# GRLV_double_Rail_v0_2b_P2.net
KiCad netlist of a schematic drawn in Altium Designer
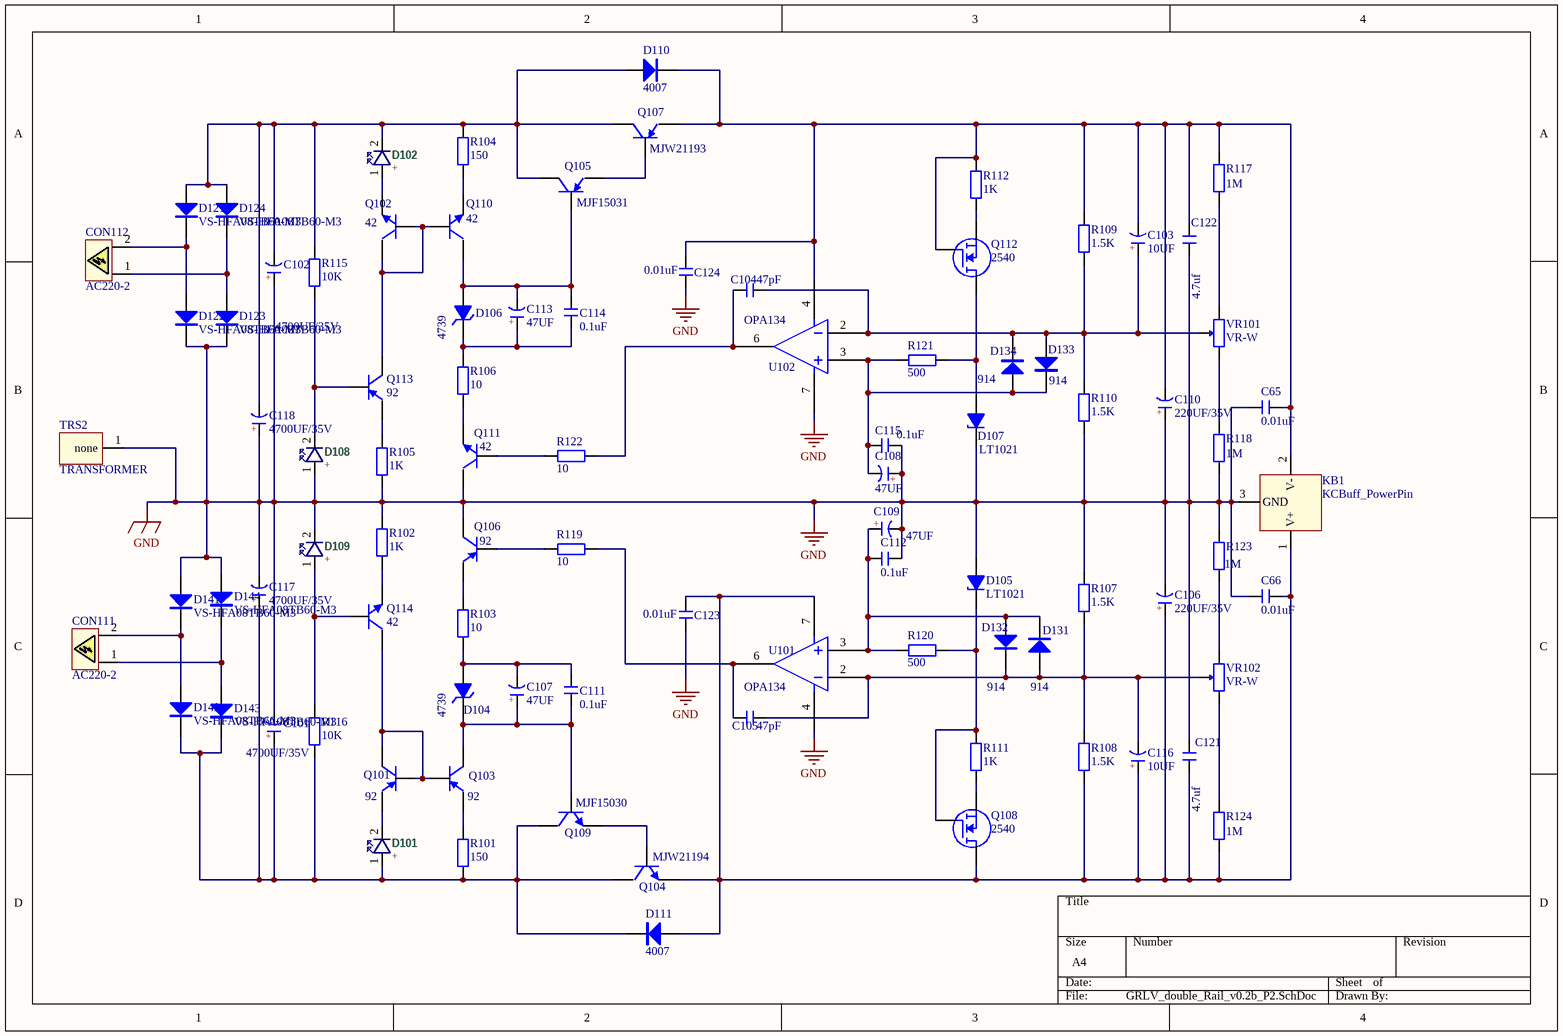
[diagram p0: GRLV_double_Rail_v0.2b_P2.SchDoc]

(export (version "E")
  (design (tool "Eeschema 10.0.6"))
  (components
    (comp (ref "C65")
      (value "0.01uF")
      (footprint "CBB 6.3*6.3*5")
      (description "CBB电容")
      (fields (field (name "版权归属") "源创客"))
      (libsource (lib "电阻-电容-电感") (part "C-CBB"))
    )
    (comp (ref "C66")
      (value "0.01uF")
      (footprint "CBB 6.3*6.3*5")
      (description "CBB电容")
      (fields (field (name "版权归属") "源创客"))
      (libsource (lib "电阻-电容-电感") (part "C-CBB"))
    )
    (comp (ref "C101")
      (value "4700UF/35V")
      (footprint "CAP 10*22*31.5")
      (description "直插电解电容")
      (fields (field (name "版权归属") "源创客"))
      (libsource (lib "电阻-电容-电感") (part "C-CAP"))
    )
    (comp (ref "C102")
      (value "4700UF/35V")
      (footprint "CAP 10*22*31.5")
      (description "直插电解电容")
      (fields (field (name "版权归属") "源创客"))
      (libsource (lib "电阻-电容-电感") (part "C-CAP"))
    )
    (comp (ref "C103")
      (value "10UF")
      (footprint "CAP 2.5*6.3*7")
      (description "直插电解电容")
      (fields (field (name "版权归属") "源创客"))
      (libsource (lib "电阻-电容-电感") (part "C-CAP"))
    )
    (comp (ref "C104")
      (value "47pF")
      (footprint "CBB 6.3*6.3*5")
      (description "CBB电容")
      (fields (field (name "版权归属") "源创客"))
      (libsource (lib "电阻-电容-电感") (part "C-CBB"))
    )
    (comp (ref "C105")
      (value "47pF")
      (footprint "CBB 6.3*6.3*5")
      (description "CBB电容")
      (fields (field (name "版权归属") "源创客"))
      (libsource (lib "电阻-电容-电感") (part "C-CBB"))
    )
    (comp (ref "C106")
      (value "220UF/35V")
      (footprint "CAP 5.0*10*12.5")
      (description "直插电解电容")
      (fields (field (name "版权归属") "源创客"))
      (libsource (lib "电阻-电容-电感") (part "C-CAP"))
    )
    (comp (ref "C107")
      (value "47UF")
      (footprint "CAP 3.5*8*11.5")
      (description "直插电解电容")
      (fields (field (name "版权归属") "源创客"))
      (libsource (lib "电阻-电容-电感") (part "C-CAP"))
    )
    (comp (ref "C108")
      (value "47UF")
      (footprint "CAP 2.5*6.3*11.2")
      (description "直插电解电容")
      (fields (field (name "版权归属") "源创客"))
      (libsource (lib "") (part "C-CAP_1"))
    )
    (comp (ref "C109")
      (value "47UF")
      (footprint "CAP 2.5*6.3*11.2")
      (description "直插电解电容")
      (fields (field (name "版权归属") "源创客"))
      (libsource (lib "") (part "C-CAP_1"))
    )
    (comp (ref "C110")
      (value "220UF/35V")
      (footprint "CAP 5.0*10*12.5")
      (description "直插电解电容")
      (fields (field (name "版权归属") "源创客"))
      (libsource (lib "电阻-电容-电感") (part "C-CAP"))
    )
    (comp (ref "C111")
      (value "0.1uF")
      (footprint "CBB 6.3*6.3*5")
      (description "CBB电容")
      (fields (field (name "版权归属") "源创客"))
      (libsource (lib "电阻-电容-电感") (part "C-CBB"))
    )
    (comp (ref "C112")
      (value "0.1uF")
      (footprint "CBB 6.3*6.3*5")
      (description "CBB电容")
      (fields (field (name "版权归属") "源创客"))
      (libsource (lib "电阻-电容-电感") (part "C-CBB"))
    )
    (comp (ref "C113")
      (value "47UF")
      (footprint "CAP 3.5*8*11.5")
      (description "直插电解电容")
      (fields (field (name "版权归属") "源创客"))
      (libsource (lib "电阻-电容-电感") (part "C-CAP"))
    )
    (comp (ref "C114")
      (value "0.1uF")
      (footprint "CBB 6.3*6.3*5")
      (description "CBB电容")
      (fields (field (name "版权归属") "源创客"))
      (libsource (lib "电阻-电容-电感") (part "C-CBB"))
    )
    (comp (ref "C115")
      (value "0.1uF")
      (footprint "CBB 6.3*6.3*5")
      (description "CBB电容")
      (fields (field (name "版权归属") "源创客"))
      (libsource (lib "电阻-电容-电感") (part "C-CBB"))
    )
    (comp (ref "C116")
      (value "10UF")
      (footprint "CAP 2.5*6.3*7")
      (description "直插电解电容")
      (fields (field (name "版权归属") "源创客"))
      (libsource (lib "电阻-电容-电感") (part "C-CAP"))
    )
    (comp (ref "C117")
      (value "4700UF/35V")
      (footprint "CAP 10*22*31.5")
      (description "直插电解电容")
      (fields (field (name "版权归属") "源创客"))
      (libsource (lib "电阻-电容-电感") (part "C-CAP"))
    )
    (comp (ref "C118")
      (value "4700UF/35V")
      (footprint "CAP 10*22*31.5")
      (description "直插电解电容")
      (fields (field (name "版权归属") "源创客"))
      (libsource (lib "电阻-电容-电感") (part "C-CAP"))
    )
    (comp (ref "C121")
      (value "4.7uf")
      (footprint "CBB 7.2*7.2*13")
      (description "MKS薄膜电容")
      (libsource (lib "电阻-电容-电感") (part "C-MKS"))
    )
    (comp (ref "C122")
      (value "4.7uf")
      (footprint "CBB 7.2*7.2*13")
      (description "MKS薄膜电容")
      (libsource (lib "电阻-电容-电感") (part "C-MKS"))
    )
    (comp (ref "C123")
      (value "0.01uF")
      (footprint "CBB 6.3*6.3*5")
      (description "CBB电容")
      (fields (field (name "Comment") ".01") (field (name "版权归属") "源创客"))
      (libsource (lib "电阻-电容-电感") (part "C-CBB"))
    )
    (comp (ref "C124")
      (value "0.01uF")
      (footprint "CBB 6.3*6.3*5")
      (description "CBB电容")
      (fields (field (name "Comment") ".01") (field (name "版权归属") "源创客"))
      (libsource (lib "电阻-电容-电感") (part "C-CBB"))
    )
    (comp (ref "CON111")
      (value "AC220-2")
      (footprint "HX4.0-2XS")
      (libsource (lib "Connectors") (part "AC220-2"))
    )
    (comp (ref "CON112")
      (value "AC220-2")
      (footprint "HX4.0-2XS")
      (libsource (lib "Connectors") (part "AC220-2"))
    )
    (comp (ref "D101")
      (value "+")
      (footprint "LED 3MM-R")
      (description "直插式LED")
      (libsource (lib "LED") (part "LED"))
    )
    (comp (ref "D102")
      (value "+")
      (footprint "LED 3MM-R")
      (description "直插式LED")
      (libsource (lib "LED") (part "LED"))
    )
    (comp (ref "D104")
      (value "4739")
      (footprint "DO-41")
      (description "9.1V/1W稳压管")
      (libsource (lib "二极管-整流桥") (part "1N4739"))
    )
    (comp (ref "D105")
      (value "LT1021")
      (footprint "DIP8-300_MH")
      (description "10V Precision Reference 2 Pin Config")
      (libsource (lib "电压参考") (part "LT1021-10-2P"))
    )
    (comp (ref "D106")
      (value "4739")
      (footprint "DO-41")
      (description "9.1V/1W稳压管")
      (libsource (lib "二极管-整流桥") (part "1N4739"))
    )
    (comp (ref "D107")
      (value "LT1021")
      (footprint "DIP8-300_MH")
      (description "10V Precision Reference 2 Pin Config")
      (libsource (lib "电压参考") (part "LT1021-10-2P"))
    )
    (comp (ref "D108")
      (value "+")
      (footprint "LED 3MM-R")
      (description "直插式LED")
      (libsource (lib "LED") (part "LED"))
    )
    (comp (ref "D109")
      (value "+")
      (footprint "LED 3MM-R")
      (description "直插式LED")
      (libsource (lib "LED") (part "LED"))
    )
    (comp (ref "D110")
      (value "4007")
      (footprint "DO-41")
      (description "整流二极管")
      (fields (field (name "版权归属") "源创客"))
      (libsource (lib "二极管-整流桥") (part "1N4007"))
    )
    (comp (ref "D111")
      (value "4007")
      (footprint "DO-41")
      (description "整流二极管")
      (fields (field (name "版权归属") "源创客"))
      (libsource (lib "二极管-整流桥") (part "1N4007"))
    )
    (comp (ref "D121")
      (value "VS-HFA08TB60-M3")
      (footprint "DO-15XL")
      (description "Ultrafast Soft Recovery Diado 8A 600V")
      (libsource (lib "二极管-整流桥") (part "VS-HFA08TB60-M3"))
    )
    (comp (ref "D122")
      (value "VS-HFA08TB60-M3")
      (footprint "DO-15XL")
      (description "Ultrafast Soft Recovery Diado 8A 600V")
      (libsource (lib "二极管-整流桥") (part "VS-HFA08TB60-M3"))
    )
    (comp (ref "D123")
      (value "VS-HFA08TB60-M3")
      (footprint "DO-15XL")
      (description "Ultrafast Soft Recovery Diado 8A 600V")
      (libsource (lib "二极管-整流桥") (part "VS-HFA08TB60-M3"))
    )
    (comp (ref "D124")
      (value "VS-HFA08TB60-M3")
      (footprint "DO-15XL")
      (description "Ultrafast Soft Recovery Diado 8A 600V")
      (libsource (lib "二极管-整流桥") (part "VS-HFA08TB60-M3"))
    )
    (comp (ref "D131")
      (value "914")
      (footprint "DO-35")
      (description "高速开关管 1V/0.25W")
      (libsource (lib "二极管-整流桥") (part "1N914"))
    )
    (comp (ref "D132")
      (value "914")
      (footprint "DO-35")
      (description "高速开关管 1V/0.25W")
      (libsource (lib "二极管-整流桥") (part "1N914"))
    )
    (comp (ref "D133")
      (value "914")
      (footprint "DO-35")
      (description "高速开关管 1V/0.25W")
      (libsource (lib "二极管-整流桥") (part "1N914"))
    )
    (comp (ref "D134")
      (value "914")
      (footprint "DO-35")
      (description "高速开关管 1V/0.25W")
      (libsource (lib "二极管-整流桥") (part "1N914"))
    )
    (comp (ref "D141")
      (value "VS-HFA08TB60-M3")
      (footprint "DO-15XL")
      (description "Ultrafast Soft Recovery Diado 8A 600V")
      (libsource (lib "二极管-整流桥") (part "VS-HFA08TB60-M3"))
    )
    (comp (ref "D142")
      (value "VS-HFA08TB60-M3")
      (footprint "DO-15XL")
      (description "Ultrafast Soft Recovery Diado 8A 600V")
      (libsource (lib "二极管-整流桥") (part "VS-HFA08TB60-M3"))
    )
    (comp (ref "D143")
      (value "VS-HFA08TB60-M3")
      (footprint "DO-15XL")
      (description "Ultrafast Soft Recovery Diado 8A 600V")
      (libsource (lib "二极管-整流桥") (part "VS-HFA08TB60-M3"))
    )
    (comp (ref "D144")
      (value "VS-HFA08TB60-M3")
      (footprint "DO-15XL")
      (description "Ultrafast Soft Recovery Diado 8A 600V")
      (libsource (lib "二极管-整流桥") (part "VS-HFA08TB60-M3"))
    )
    (comp (ref "KB1")
      (value "KCBuff_PowerPin")
      (footprint "KCBuff_PowerPin_M4")
      (description "King Cello Buffer Stage")
      (libsource (lib "KC_amp") (part "KCBuff_PowerPin"))
    )
    (comp (ref "Q101")
      (value "92")
      (footprint "TO92A")
      (description "High Voltage PNP Transistor")
      (libsource (lib "三极管") (part "KSP92/93"))
    )
    (comp (ref "Q102")
      (value "42")
      (footprint "TO92A")
      (description "High Voltage NPN Transistor")
      (libsource (lib "三极管") (part "KSP42/43"))
    )
    (comp (ref "Q103")
      (value "92")
      (footprint "TO92A")
      (description "High Voltage PNP Transistor")
      (libsource (lib "三极管") (part "KSP92/93"))
    )
    (comp (ref "Q104")
      (value "MJW21194")
      (footprint "TO247V")
      (description "Power NPN Transistor")
      (libsource (lib "三极管") (part "MJW21194"))
    )
    (comp (ref "Q105")
      (value "MJF15031")
      (footprint "TO220V")
      (description "Power PNP Transistor")
      (libsource (lib "三极管") (part "MJF15031"))
    )
    (comp (ref "Q106")
      (value "92")
      (footprint "TO92A")
      (description "High Voltage PNP Transistor")
      (libsource (lib "三极管") (part "KSP92/93"))
    )
    (comp (ref "Q107")
      (value "MJW21193")
      (footprint "TO247V")
      (description "Power PNP Transistor")
      (libsource (lib "三极管") (part "MJW21193"))
    )
    (comp (ref "Q108")
      (value "2540")
      (footprint "TO92A")
      (description "N沟道耗尽型DMOS场效应管 400V/150ma")
      (libsource (lib "场效应管") (part "DN2540"))
    )
    (comp (ref "Q109")
      (value "MJF15030")
      (footprint "TO220V")
      (description "Power NPN Transistor")
      (libsource (lib "三极管") (part "MJF15030"))
    )
    (comp (ref "Q110")
      (value "42")
      (footprint "TO92A")
      (description "High Voltage NPN Transistor")
      (libsource (lib "三极管") (part "KSP42/43"))
    )
    (comp (ref "Q111")
      (value "42")
      (footprint "TO92A")
      (description "High Voltage NPN Transistor")
      (libsource (lib "三极管") (part "KSP42/43"))
    )
    (comp (ref "Q112")
      (value "2540")
      (footprint "TO92A")
      (description "N沟道耗尽型DMOS场效应管 400V/150ma")
      (libsource (lib "场效应管") (part "DN2540"))
    )
    (comp (ref "Q113")
      (value "92")
      (footprint "TO92A")
      (description "High Voltage PNP Transistor")
      (libsource (lib "三极管") (part "KSP92/93"))
    )
    (comp (ref "Q114")
      (value "42")
      (footprint "TO92A")
      (description "High Voltage NPN Transistor")
      (libsource (lib "三极管") (part "KSP42/43"))
    )
    (comp (ref "R101")
      (value "150")
      (footprint "RS 1/4W")
      (description "直插色环电阻")
      (fields (field (name "版权归属") "源创客"))
      (libsource (lib "电阻-电容-电感") (part "R-CRR"))
    )
    (comp (ref "R102")
      (value "1K")
      (footprint "RS 1/4W")
      (description "直插色环电阻")
      (fields (field (name "版权归属") "源创客"))
      (libsource (lib "电阻-电容-电感") (part "R-CRR"))
    )
    (comp (ref "R103")
      (value "10")
      (footprint "RS 1/4W")
      (description "直插色环电阻")
      (fields (field (name "版权归属") "源创客"))
      (libsource (lib "电阻-电容-电感") (part "R-CRR"))
    )
    (comp (ref "R104")
      (value "150")
      (footprint "RS 1/4W")
      (description "直插色环电阻")
      (fields (field (name "版权归属") "源创客"))
      (libsource (lib "电阻-电容-电感") (part "R-CRR"))
    )
    (comp (ref "R105")
      (value "1K")
      (footprint "RS 1/4W")
      (description "直插色环电阻")
      (fields (field (name "版权归属") "源创客"))
      (libsource (lib "电阻-电容-电感") (part "R-CRR"))
    )
    (comp (ref "R106")
      (value "10")
      (footprint "RS 1/4W")
      (description "直插色环电阻")
      (fields (field (name "版权归属") "源创客"))
      (libsource (lib "电阻-电容-电感") (part "R-CRR"))
    )
    (comp (ref "R107")
      (value "1.5K")
      (footprint "RS 1/4W")
      (description "直插色环电阻")
      (fields (field (name "版权归属") "源创客"))
      (libsource (lib "电阻-电容-电感") (part "R-CRR"))
    )
    (comp (ref "R108")
      (value "1.5K")
      (footprint "RS 1/4W")
      (description "直插色环电阻")
      (fields (field (name "版权归属") "源创客"))
      (libsource (lib "电阻-电容-电感") (part "R-CRR"))
    )
    (comp (ref "R109")
      (value "1.5K")
      (footprint "RS 1/4W")
      (description "直插色环电阻")
      (fields (field (name "版权归属") "源创客"))
      (libsource (lib "电阻-电容-电感") (part "R-CRR"))
    )
    (comp (ref "R110")
      (value "1.5K")
      (footprint "RS 1/4W")
      (description "直插色环电阻")
      (fields (field (name "版权归属") "源创客"))
      (libsource (lib "电阻-电容-电感") (part "R-CRR"))
    )
    (comp (ref "R111")
      (value "1K")
      (footprint "RS 1/4W")
      (description "直插色环电阻")
      (fields (field (name "版权归属") "源创客"))
      (libsource (lib "电阻-电容-电感") (part "R-CRR"))
    )
    (comp (ref "R112")
      (value "1K")
      (footprint "RS 1/4W")
      (description "直插色环电阻")
      (fields (field (name "版权归属") "源创客"))
      (libsource (lib "电阻-电容-电感") (part "R-CRR"))
    )
    (comp (ref "R115")
      (value "10K")
      (footprint "RS 1/4W")
      (description "直插色环电阻")
      (fields (field (name "版权归属") "源创客"))
      (libsource (lib "电阻-电容-电感") (part "R-CRR"))
    )
    (comp (ref "R116")
      (value "10K")
      (footprint "RS 1/4W")
      (description "直插色环电阻")
      (fields (field (name "版权归属") "源创客"))
      (libsource (lib "电阻-电容-电感") (part "R-CRR"))
    )
    (comp (ref "R117")
      (value "1M")
      (footprint "RS 1/4W")
      (description "直插色环电阻")
      (fields (field (name "版权归属") "源创客"))
      (libsource (lib "电阻-电容-电感") (part "R-CRR"))
    )
    (comp (ref "R118")
      (value "1M")
      (footprint "RS 1/4W")
      (description "直插色环电阻")
      (fields (field (name "版权归属") "源创客"))
      (libsource (lib "电阻-电容-电感") (part "R-CRR"))
    )
    (comp (ref "R119")
      (value "10")
      (footprint "RS 1/4W")
      (description "直插色环电阻")
      (fields (field (name "版权归属") "源创客"))
      (libsource (lib "电阻-电容-电感") (part "R-CRR"))
    )
    (comp (ref "R120")
      (value "500")
      (footprint "RS 1/4W")
      (description "直插色环电阻")
      (fields (field (name "版权归属") "源创客"))
      (libsource (lib "电阻-电容-电感") (part "R-CRR"))
    )
    (comp (ref "R121")
      (value "500")
      (footprint "RS 1/4W")
      (description "直插色环电阻")
      (fields (field (name "版权归属") "源创客"))
      (libsource (lib "电阻-电容-电感") (part "R-CRR"))
    )
    (comp (ref "R122")
      (value "10")
      (footprint "RS 1/4W")
      (description "直插色环电阻")
      (fields (field (name "版权归属") "源创客"))
      (libsource (lib "电阻-电容-电感") (part "R-CRR"))
    )
    (comp (ref "R123")
      (value "1M")
      (footprint "RS 1/4W")
      (description "直插色环电阻")
      (fields (field (name "版权归属") "源创客"))
      (libsource (lib "电阻-电容-电感") (part "R-CRR"))
    )
    (comp (ref "R124")
      (value "1M")
      (footprint "RS 1/4W")
      (description "直插色环电阻")
      (fields (field (name "版权归属") "源创客"))
      (libsource (lib "电阻-电容-电感") (part "R-CRR"))
    )
    (comp (ref "TRS2")
      (value "TRANSFORMER")
      (footprint "TRANS_BLOCK_30W_24v")
      (description "Transformer")
      (libsource (lib "KC_amp") (part "TRANSFORMER"))
    )
    (comp (ref "U101") (value "OPA134") (footprint "DIP8-300_MH") (libsource (lib "运放") (part "OPA134PA")))
    (comp (ref "U102") (value "OPA134") (footprint "DIP8-300_MH") (libsource (lib "运放") (part "OPA134PA")))
    (comp (ref "VR101")
      (value "VR-W")
      (footprint "RS 1/2W-VR")
      (description "直插可调电阻-顶调")
      (libsource (lib "电阻-电容-电感") (part "VR-W"))
    )
    (comp (ref "VR102")
      (value "VR-W")
      (footprint "RS 1/2W-VR")
      (description "直插可调电阻-顶调")
      (libsource (lib "电阻-电容-电感") (part "VR-W"))
    )
  )
  (nets
    (net (code "1") (name "GND") (class "Default")
      (node (ref "C101") (pin "2") (pinfunction "K_2") (pintype "passive"))
      (node (ref "C102") (pin "1") (pinfunction "A_1") (pintype "passive"))
      (node (ref "C106") (pin "2") (pinfunction "K_2") (pintype "passive"))
      (node (ref "C108") (pin "1") (pinfunction "A_1") (pintype "passive"))
      (node (ref "C109") (pin "2") (pinfunction "K_2") (pintype "passive"))
      (node (ref "C110") (pin "1") (pinfunction "A_1") (pintype "passive"))
      (node (ref "C112") (pin "2") (pinfunction "2_2") (pintype "passive"))
      (node (ref "C115") (pin "2") (pinfunction "2_2") (pintype "passive"))
      (node (ref "C117") (pin "2") (pinfunction "K_2") (pintype "passive"))
      (node (ref "C118") (pin "1") (pinfunction "A_1") (pintype "passive"))
      (node (ref "C121") (pin "2") (pinfunction "2_2") (pintype "passive"))
      (node (ref "C122") (pin "1") (pinfunction "1_1") (pintype "passive"))
      (node (ref "C123") (pin "1") (pinfunction "1_1") (pintype "passive"))
      (node (ref "C124") (pin "1") (pinfunction "1_1") (pintype "passive"))
      (node (ref "C65") (pin "1") (pinfunction "1_1") (pintype "passive"))
      (node (ref "C66") (pin "1") (pinfunction "1_1") (pintype "passive"))
      (node (ref "D105") (pin "4") (pinfunction "A_4") (pintype "passive"))
      (node (ref "D107") (pin "6") (pinfunction "K_6") (pintype "passive"))
      (node (ref "D108") (pin "1") (pinfunction "A_1") (pintype "passive"))
      (node (ref "D109") (pin "2") (pinfunction "K_2") (pintype "passive"))
      (node (ref "D122") (pin "1") (pinfunction "Cathode_1") (pintype "passive"))
      (node (ref "D123") (pin "1") (pinfunction "Cathode_1") (pintype "passive"))
      (node (ref "D141") (pin "2") (pinfunction "Anode_2") (pintype "passive"))
      (node (ref "D144") (pin "2") (pinfunction "Anode_2") (pintype "passive"))
      (node (ref "KB1") (pin "3") (pinfunction "GND_3") (pintype "passive"))
      (node (ref "Q106") (pin "3") (pinfunction "C_3") (pintype "passive"))
      (node (ref "Q111") (pin "3") (pinfunction "C_3") (pintype "passive"))
      (node (ref "R102") (pin "2") (pinfunction "2_2") (pintype "passive"))
      (node (ref "R105") (pin "1") (pinfunction "1_1") (pintype "passive"))
      (node (ref "R107") (pin "2") (pinfunction "2_2") (pintype "passive"))
      (node (ref "R110") (pin "1") (pinfunction "1_1") (pintype "passive"))
      (node (ref "R118") (pin "1") (pinfunction "1_1") (pintype "passive"))
      (node (ref "R123") (pin "2") (pinfunction "2_2") (pintype "passive"))
      (node (ref "TRS2") (pin "1") (pinfunction "none_1") (pintype "passive"))
      (node (ref "U101") (pin "4") (pinfunction "V-_4") (pintype "passive"))
      (node (ref "U102") (pin "7") (pinfunction "V+_7") (pintype "passive"))
    )
    (net (code "2") (name "Net-(C101-A)") (class "Default")
      (node (ref "C101") (pin "1") (pinfunction "A_1") (pintype "passive"))
      (node (ref "C117") (pin "1") (pinfunction "A_1") (pintype "passive"))
      (node (ref "D101") (pin "1") (pinfunction "A_1") (pintype "passive"))
      (node (ref "D111") (pin "2") (pinfunction "K_2") (pintype "passive"))
      (node (ref "D142") (pin "1") (pinfunction "Cathode_1") (pintype "passive"))
      (node (ref "D143") (pin "1") (pinfunction "Cathode_1") (pintype "passive"))
      (node (ref "Q104") (pin "2") (pinfunction "C_2") (pintype "passive"))
      (node (ref "Q109") (pin "2") (pinfunction "C_2") (pintype "passive"))
      (node (ref "R101") (pin "1") (pinfunction "1_1") (pintype "passive"))
      (node (ref "R116") (pin "1") (pinfunction "1_1") (pintype "passive"))
    )
    (net (code "3") (name "Net-(C102-K)") (class "Default")
      (node (ref "C102") (pin "2") (pinfunction "K_2") (pintype "passive"))
      (node (ref "C118") (pin "2") (pinfunction "K_2") (pintype "passive"))
      (node (ref "D102") (pin "2") (pinfunction "K_2") (pintype "passive"))
      (node (ref "D110") (pin "1") (pinfunction "A_1") (pintype "passive"))
      (node (ref "D121") (pin "2") (pinfunction "Anode_2") (pintype "passive"))
      (node (ref "D124") (pin "2") (pinfunction "Anode_2") (pintype "passive"))
      (node (ref "Q105") (pin "2") (pinfunction "C_2") (pintype "passive"))
      (node (ref "Q107") (pin "2") (pinfunction "C_2") (pintype "passive"))
      (node (ref "R104") (pin "2") (pinfunction "2_2") (pintype "passive"))
      (node (ref "R115") (pin "2") (pinfunction "2_2") (pintype "passive"))
    )
    (net (code "4") (name "Net-(C103-A)") (class "Default")
      (node (ref "C103") (pin "1") (pinfunction "A_1") (pintype "passive"))
      (node (ref "C104") (pin "2") (pinfunction "2_2") (pintype "passive"))
      (node (ref "D133") (pin "1") (pinfunction "A_1") (pintype "passive"))
      (node (ref "D134") (pin "2") (pinfunction "K_2") (pintype "passive"))
      (node (ref "R109") (pin "1") (pinfunction "1_1") (pintype "passive"))
      (node (ref "R110") (pin "2") (pinfunction "2_2") (pintype "passive"))
      (node (ref "U102") (pin "2") (pinfunction "-in_2") (pintype "passive"))
      (node (ref "VR101") (pin "3") (pinfunction "3_3") (pintype "passive"))
    )
    (net (code "5") (name "Net-(C103-K)") (class "Default")
      (node (ref "C103") (pin "2") (pinfunction "K_2") (pintype "passive"))
      (node (ref "C110") (pin "2") (pinfunction "K_2") (pintype "passive"))
      (node (ref "C122") (pin "2") (pinfunction "2_2") (pintype "passive"))
      (node (ref "C124") (pin "2") (pinfunction "2_2") (pintype "passive"))
      (node (ref "C65") (pin "2") (pinfunction "2_2") (pintype "passive"))
      (node (ref "D110") (pin "2") (pinfunction "K_2") (pintype "passive"))
      (node (ref "KB1") (pin "2") (pinfunction "V-_2") (pintype "passive"))
      (node (ref "Q107") (pin "3") (pinfunction "E_3") (pintype "passive"))
      (node (ref "Q112") (pin "2") (pinfunction "G_2") (pintype "passive"))
      (node (ref "R109") (pin "2") (pinfunction "2_2") (pintype "passive"))
      (node (ref "R112") (pin "2") (pinfunction "2_2") (pintype "passive"))
      (node (ref "R117") (pin "2") (pinfunction "2_2") (pintype "passive"))
      (node (ref "U102") (pin "4") (pinfunction "V-_4") (pintype "passive"))
    )
    (net (code "6") (name "Net-(C106-A)") (class "Default")
      (node (ref "C106") (pin "1") (pinfunction "A_1") (pintype "passive"))
      (node (ref "C116") (pin "1") (pinfunction "A_1") (pintype "passive"))
      (node (ref "C121") (pin "1") (pinfunction "1_1") (pintype "passive"))
      (node (ref "C123") (pin "2") (pinfunction "2_2") (pintype "passive"))
      (node (ref "C66") (pin "2") (pinfunction "2_2") (pintype "passive"))
      (node (ref "D111") (pin "1") (pinfunction "A_1") (pintype "passive"))
      (node (ref "KB1") (pin "1") (pinfunction "V+_1") (pintype "passive"))
      (node (ref "Q104") (pin "3") (pinfunction "E_3") (pintype "passive"))
      (node (ref "Q108") (pin "3") (pinfunction "D_3") (pintype "passive"))
      (node (ref "R108") (pin "1") (pinfunction "1_1") (pintype "passive"))
      (node (ref "R124") (pin "1") (pinfunction "1_1") (pintype "passive"))
      (node (ref "U101") (pin "7") (pinfunction "V+_7") (pintype "passive"))
    )
    (net (code "7") (name "Net-(C107-A)") (class "Default")
      (node (ref "C107") (pin "1") (pinfunction "A_1") (pintype "passive"))
      (node (ref "C111") (pin "1") (pinfunction "1_1") (pintype "passive"))
      (node (ref "D104") (pin "2") (pinfunction "K_2") (pintype "passive"))
      (node (ref "Q103") (pin "3") (pinfunction "C_3") (pintype "passive"))
      (node (ref "Q109") (pin "1") (pinfunction "B_1") (pintype "passive"))
    )
    (net (code "8") (name "Net-(C107-K)") (class "Default")
      (node (ref "C107") (pin "2") (pinfunction "K_2") (pintype "passive"))
      (node (ref "C111") (pin "2") (pinfunction "2_2") (pintype "passive"))
      (node (ref "D104") (pin "1") (pinfunction "A_1") (pintype "passive"))
      (node (ref "R103") (pin "1") (pinfunction "1_1") (pintype "passive"))
    )
    (net (code "9") (name "Net-(C108-K)") (class "Default")
      (node (ref "C108") (pin "2") (pinfunction "K_2") (pintype "passive"))
      (node (ref "C115") (pin "1") (pinfunction "1_1") (pintype "passive"))
      (node (ref "D133") (pin "2") (pinfunction "K_2") (pintype "passive"))
      (node (ref "D134") (pin "1") (pinfunction "A_1") (pintype "passive"))
      (node (ref "R121") (pin "1") (pinfunction "1_1") (pintype "passive"))
      (node (ref "U102") (pin "3") (pinfunction "+in_3") (pintype "passive"))
    )
    (net (code "10") (name "Net-(C109-A)") (class "Default")
      (node (ref "C109") (pin "1") (pinfunction "A_1") (pintype "passive"))
      (node (ref "C112") (pin "1") (pinfunction "1_1") (pintype "passive"))
      (node (ref "D131") (pin "2") (pinfunction "K_2") (pintype "passive"))
      (node (ref "D132") (pin "1") (pinfunction "A_1") (pintype "passive"))
      (node (ref "R120") (pin "1") (pinfunction "1_1") (pintype "passive"))
      (node (ref "U101") (pin "3") (pinfunction "+in_3") (pintype "passive"))
    )
    (net (code "11") (name "Net-(C113-A)") (class "Default")
      (node (ref "C113") (pin "1") (pinfunction "A_1") (pintype "passive"))
      (node (ref "C114") (pin "1") (pinfunction "1_1") (pintype "passive"))
      (node (ref "D106") (pin "2") (pinfunction "K_2") (pintype "passive"))
      (node (ref "R106") (pin "2") (pinfunction "2_2") (pintype "passive"))
    )
    (net (code "12") (name "Net-(C113-K)") (class "Default")
      (node (ref "C113") (pin "2") (pinfunction "K_2") (pintype "passive"))
      (node (ref "C114") (pin "2") (pinfunction "2_2") (pintype "passive"))
      (node (ref "D106") (pin "1") (pinfunction "A_1") (pintype "passive"))
      (node (ref "Q105") (pin "1") (pinfunction "B_1") (pintype "passive"))
      (node (ref "Q110") (pin "3") (pinfunction "C_3") (pintype "passive"))
    )
    (net (code "13") (name "Net-(C116-K)") (class "Default")
      (node (ref "C105") (pin "2") (pinfunction "2_2") (pintype "passive"))
      (node (ref "C116") (pin "2") (pinfunction "K_2") (pintype "passive"))
      (node (ref "D131") (pin "1") (pinfunction "A_1") (pintype "passive"))
      (node (ref "D132") (pin "2") (pinfunction "K_2") (pintype "passive"))
      (node (ref "R107") (pin "1") (pinfunction "1_1") (pintype "passive"))
      (node (ref "R108") (pin "2") (pinfunction "2_2") (pintype "passive"))
      (node (ref "U101") (pin "2") (pinfunction "-in_2") (pintype "passive"))
      (node (ref "VR102") (pin "3") (pinfunction "3_3") (pintype "passive"))
    )
    (net (code "14") (name "Net-(CON111-G)") (class "Default")
      (node (ref "CON111") (pin "2") (pinfunction "G_2") (pintype "passive"))
      (node (ref "D141") (pin "1") (pinfunction "Cathode_1") (pintype "passive"))
      (node (ref "D142") (pin "2") (pinfunction "Anode_2") (pintype "passive"))
    )
    (net (code "15") (name "Net-(CON111-L)") (class "Default")
      (node (ref "CON111") (pin "1") (pinfunction "L_1") (pintype "passive"))
      (node (ref "D143") (pin "2") (pinfunction "Anode_2") (pintype "passive"))
      (node (ref "D144") (pin "1") (pinfunction "Cathode_1") (pintype "passive"))
    )
    (net (code "16") (name "Net-(CON112-G)") (class "Default")
      (node (ref "CON112") (pin "2") (pinfunction "G_2") (pintype "passive"))
      (node (ref "D121") (pin "1") (pinfunction "Cathode_1") (pintype "passive"))
      (node (ref "D122") (pin "2") (pinfunction "Anode_2") (pintype "passive"))
    )
    (net (code "17") (name "Net-(CON112-L)") (class "Default")
      (node (ref "CON112") (pin "1") (pinfunction "L_1") (pintype "passive"))
      (node (ref "D123") (pin "2") (pinfunction "Anode_2") (pintype "passive"))
      (node (ref "D124") (pin "1") (pinfunction "Cathode_1") (pintype "passive"))
    )
    (net (code "18") (name "Net-(D101-K)") (class "Default")
      (node (ref "D101") (pin "2") (pinfunction "K_2") (pintype "passive"))
      (node (ref "Q101") (pin "1") (pinfunction "E_1") (pintype "passive"))
    )
    (net (code "19") (name "Net-(D102-A)") (class "Default")
      (node (ref "D102") (pin "1") (pinfunction "A_1") (pintype "passive"))
      (node (ref "Q102") (pin "1") (pinfunction "E_1") (pintype "passive"))
    )
    (net (code "20") (name "Net-(D105-K)") (class "Default")
      (node (ref "D105") (pin "6") (pinfunction "K_6") (pintype "passive"))
      (node (ref "Q108") (pin "2") (pinfunction "G_2") (pintype "passive"))
      (node (ref "R111") (pin "2") (pinfunction "2_2") (pintype "passive"))
      (node (ref "R120") (pin "2") (pinfunction "2_2") (pintype "passive"))
    )
    (net (code "21") (name "Net-(D107-A)") (class "Default")
      (node (ref "D107") (pin "4") (pinfunction "A_4") (pintype "passive"))
      (node (ref "Q112") (pin "3") (pinfunction "D_3") (pintype "passive"))
      (node (ref "R121") (pin "2") (pinfunction "2_2") (pintype "passive"))
    )
    (net (code "22") (name "Net-(D108-K)") (class "Default")
      (node (ref "D108") (pin "2") (pinfunction "K_2") (pintype "passive"))
      (node (ref "Q113") (pin "2") (pinfunction "B_2") (pintype "passive"))
      (node (ref "R115") (pin "1") (pinfunction "1_1") (pintype "passive"))
    )
    (net (code "23") (name "Net-(D109-A)") (class "Default")
      (node (ref "D109") (pin "1") (pinfunction "A_1") (pintype "passive"))
      (node (ref "Q114") (pin "2") (pinfunction "B_2") (pintype "passive"))
      (node (ref "R116") (pin "2") (pinfunction "2_2") (pintype "passive"))
    )
    (net (code "24") (name "Net-(Q101-B)") (class "Default")
      (node (ref "Q101") (pin "2") (pinfunction "B_2") (pintype "passive"))
      (node (ref "Q101") (pin "3") (pinfunction "C_3") (pintype "passive"))
      (node (ref "Q103") (pin "2") (pinfunction "B_2") (pintype "passive"))
      (node (ref "Q114") (pin "3") (pinfunction "C_3") (pintype "passive"))
    )
    (net (code "25") (name "Net-(Q102-B)") (class "Default")
      (node (ref "Q102") (pin "2") (pinfunction "B_2") (pintype "passive"))
      (node (ref "Q102") (pin "3") (pinfunction "C_3") (pintype "passive"))
      (node (ref "Q110") (pin "2") (pinfunction "B_2") (pintype "passive"))
      (node (ref "Q113") (pin "3") (pinfunction "C_3") (pintype "passive"))
    )
    (net (code "26") (name "Net-(Q103-E)") (class "Default")
      (node (ref "Q103") (pin "1") (pinfunction "E_1") (pintype "passive"))
      (node (ref "R101") (pin "2") (pinfunction "2_2") (pintype "passive"))
    )
    (net (code "27") (name "Net-(Q104-B)") (class "Default")
      (node (ref "Q104") (pin "1") (pinfunction "B_1") (pintype "passive"))
      (node (ref "Q109") (pin "3") (pinfunction "E_3") (pintype "passive"))
    )
    (net (code "28") (name "Net-(Q105-E)") (class "Default")
      (node (ref "Q105") (pin "3") (pinfunction "E_3") (pintype "passive"))
      (node (ref "Q107") (pin "1") (pinfunction "B_1") (pintype "passive"))
    )
    (net (code "29") (name "Net-(Q106-B)") (class "Default")
      (node (ref "Q106") (pin "2") (pinfunction "B_2") (pintype "passive"))
      (node (ref "R119") (pin "1") (pinfunction "1_1") (pintype "passive"))
    )
    (net (code "30") (name "Net-(Q106-E)") (class "Default")
      (node (ref "Q106") (pin "1") (pinfunction "E_1") (pintype "passive"))
      (node (ref "R103") (pin "2") (pinfunction "2_2") (pintype "passive"))
    )
    (net (code "31") (name "Net-(Q108-S)") (class "Default")
      (node (ref "Q108") (pin "1") (pinfunction "S_1") (pintype "passive"))
      (node (ref "R111") (pin "1") (pinfunction "1_1") (pintype "passive"))
    )
    (net (code "32") (name "Net-(Q110-E)") (class "Default")
      (node (ref "Q110") (pin "1") (pinfunction "E_1") (pintype "passive"))
      (node (ref "R104") (pin "1") (pinfunction "1_1") (pintype "passive"))
    )
    (net (code "33") (name "Net-(Q111-B)") (class "Default")
      (node (ref "Q111") (pin "2") (pinfunction "B_2") (pintype "passive"))
      (node (ref "R122") (pin "1") (pinfunction "1_1") (pintype "passive"))
    )
    (net (code "34") (name "Net-(Q111-E)") (class "Default")
      (node (ref "Q111") (pin "1") (pinfunction "E_1") (pintype "passive"))
      (node (ref "R106") (pin "1") (pinfunction "1_1") (pintype "passive"))
    )
    (net (code "35") (name "Net-(Q112-S)") (class "Default")
      (node (ref "Q112") (pin "1") (pinfunction "S_1") (pintype "passive"))
      (node (ref "R112") (pin "1") (pinfunction "1_1") (pintype "passive"))
    )
    (net (code "36") (name "Net-(Q113-E)") (class "Default")
      (node (ref "Q113") (pin "1") (pinfunction "E_1") (pintype "passive"))
      (node (ref "R105") (pin "2") (pinfunction "2_2") (pintype "passive"))
    )
    (net (code "37") (name "Net-(Q114-E)") (class "Default")
      (node (ref "Q114") (pin "1") (pinfunction "E_1") (pintype "passive"))
      (node (ref "R102") (pin "1") (pinfunction "1_1") (pintype "passive"))
    )
    (net (code "38") (name "Net-(R117-Pad1)") (class "Default")
      (node (ref "R117") (pin "1") (pinfunction "1_1") (pintype "passive"))
      (node (ref "VR101") (pin "2") (pinfunction "2_2") (pintype "passive"))
    )
    (net (code "39") (name "Net-(R118-Pad2)") (class "Default")
      (node (ref "R118") (pin "2") (pinfunction "2_2") (pintype "passive"))
      (node (ref "VR101") (pin "1") (pinfunction "1_1") (pintype "passive"))
    )
    (net (code "40") (name "Net-(R123-Pad1)") (class "Default")
      (node (ref "R123") (pin "1") (pinfunction "1_1") (pintype "passive"))
      (node (ref "VR102") (pin "2") (pinfunction "2_2") (pintype "passive"))
    )
    (net (code "41") (name "Net-(R124-Pad2)") (class "Default")
      (node (ref "R124") (pin "2") (pinfunction "2_2") (pintype "passive"))
      (node (ref "VR102") (pin "1") (pinfunction "1_1") (pintype "passive"))
    )
    (net (code "42") (name "Net-(U101-out)") (class "Default")
      (node (ref "C105") (pin "1") (pinfunction "1_1") (pintype "passive"))
      (node (ref "R119") (pin "2") (pinfunction "2_2") (pintype "passive"))
      (node (ref "U101") (pin "6") (pinfunction "out_6") (pintype "passive"))
    )
    (net (code "43") (name "Net-(U102-out)") (class "Default")
      (node (ref "C104") (pin "1") (pinfunction "1_1") (pintype "passive"))
      (node (ref "R122") (pin "2") (pinfunction "2_2") (pintype "passive"))
      (node (ref "U102") (pin "6") (pinfunction "out_6") (pintype "passive"))
    )
  )
)
